# NES_IO_EU.net
KiCad netlist of a schematic drawn in EAGLE
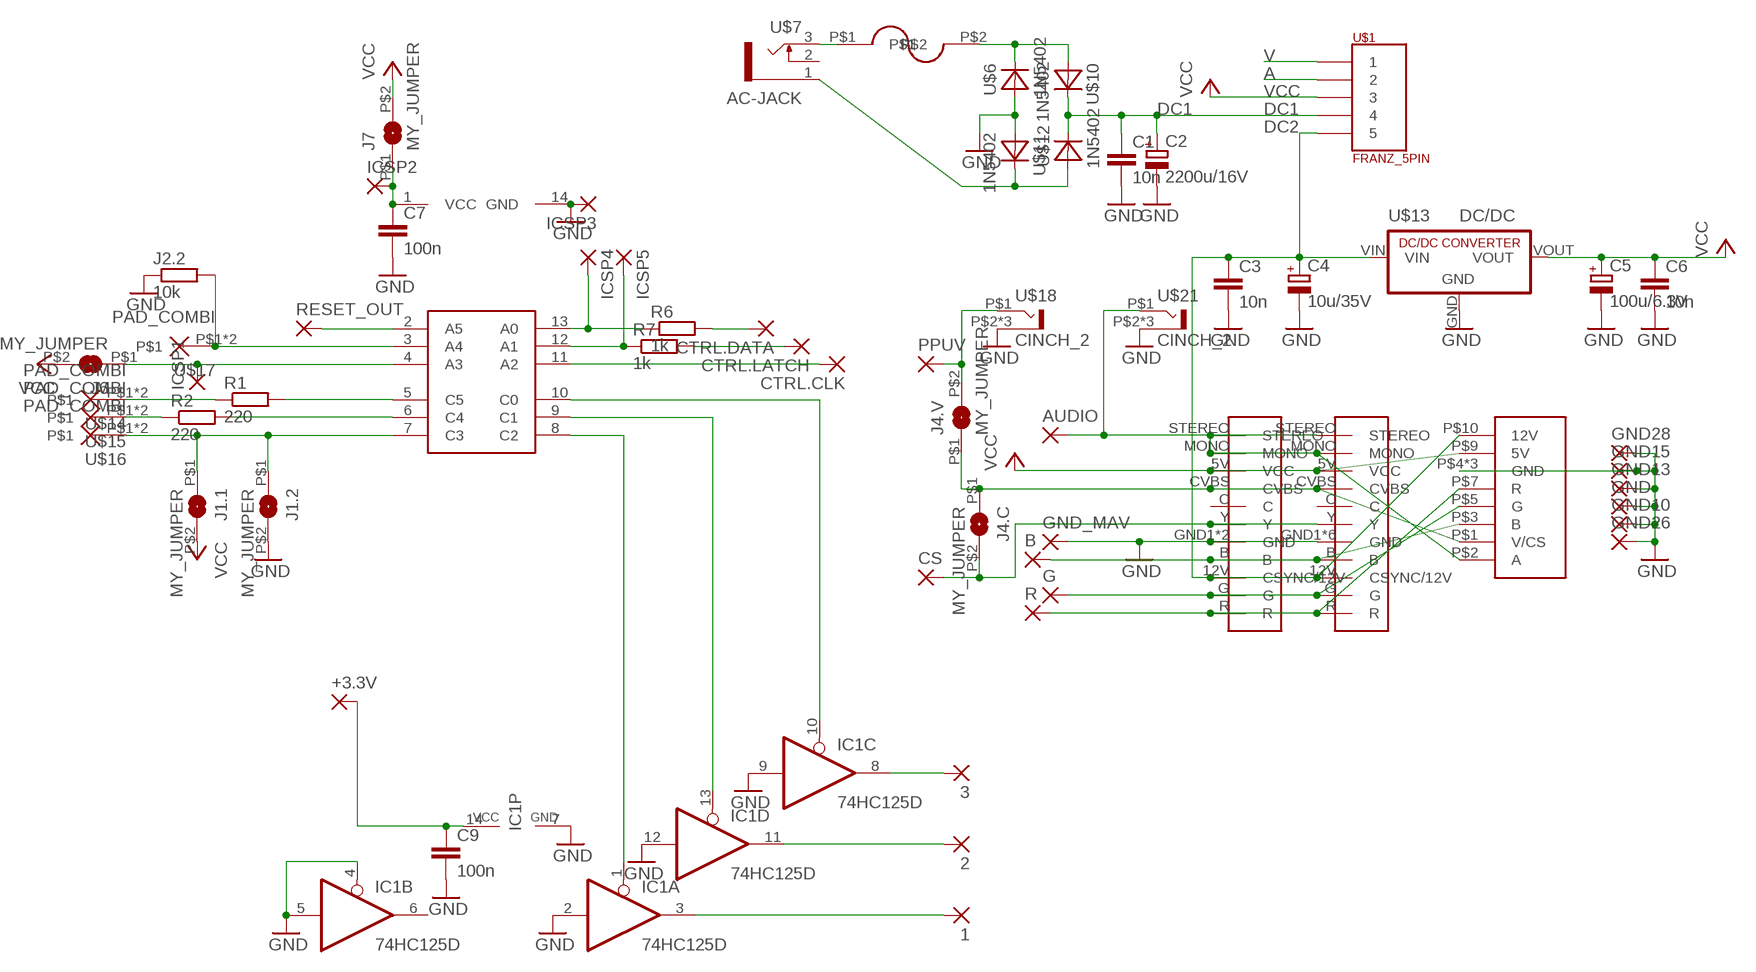
[diagram p0: schematic, sheet 1]

(export (version "E")
  (design (tool "Eeschema 10.0.6"))
  (components
    (comp (ref "+3.3V")
      (value "SMD2")
      (footprint "eagle-import:SMD1,27-2,54")
      (libsource (lib "eagle-import") (part "SMD2"))
    )
    (comp (ref "1")
      (value "SMD2")
      (footprint "eagle-import:SMD1,27-2,54")
      (libsource (lib "eagle-import") (part "SMD2"))
    )
    (comp (ref "2")
      (value "SMD2")
      (footprint "eagle-import:SMD1,27-2,54")
      (libsource (lib "eagle-import") (part "SMD2"))
    )
    (comp (ref "3")
      (value "SMD2")
      (footprint "eagle-import:SMD1,27-2,54")
      (libsource (lib "eagle-import") (part "SMD2"))
    )
    (comp (ref "AUDIO")
      (value "SMD2")
      (footprint "eagle-import:SMD1,27-2,54")
      (libsource (lib "eagle-import") (part "SMD2"))
    )
    (comp (ref "B")
      (value "SMD2")
      (footprint "eagle-import:SMD1,27-2,54")
      (libsource (lib "eagle-import") (part "SMD2"))
    )
    (comp (ref "C1")
      (value "10n")
      (footprint "eagle-import:Z0805")
      (libsource (lib "eagle-import") (part "C0805"))
    )
    (comp (ref "C2")
      (value "2200u/16V")
      (footprint "eagle-import:E5-13")
      (libsource (lib "eagle-import") (part "resistor_CPOL-EUE5-13"))
    )
    (comp (ref "C3")
      (value "10n")
      (footprint "eagle-import:Z0805")
      (libsource (lib "eagle-import") (part "C0805"))
    )
    (comp (ref "C4")
      (value "10u/35V")
      (footprint "eagle-import:PANASONIC_B")
      (libsource (lib "eagle-import") (part "CPOL-EUB"))
    )
    (comp (ref "C5")
      (value "100u/6.3V")
      (footprint "eagle-import:PANASONIC_D")
      (libsource (lib "eagle-import") (part "CPOL-EUD"))
    )
    (comp (ref "C6")
      (value "10n")
      (footprint "eagle-import:Z0805")
      (libsource (lib "eagle-import") (part "C0805"))
    )
    (comp (ref "C7")
      (value "100n")
      (footprint "eagle-import:Z0805")
      (libsource (lib "eagle-import") (part "C0805"))
    )
    (comp (ref "C9")
      (value "100n")
      (footprint "eagle-import:Z0805")
      (libsource (lib "eagle-import") (part "C0805"))
    )
    (comp (ref "CS")
      (value "SMD2")
      (footprint "eagle-import:SMD1,27-2,54")
      (libsource (lib "eagle-import") (part "SMD2"))
    )
    (comp (ref "CTRL.CLK")
      (value "SMD2")
      (footprint "eagle-import:SMD1,27-2,54")
      (libsource (lib "eagle-import") (part "SMD2"))
    )
    (comp (ref "CTRL.DATA")
      (value "SMD2")
      (footprint "eagle-import:SMD1,27-2,54")
      (libsource (lib "eagle-import") (part "SMD2"))
    )
    (comp (ref "CTRL.LATCH")
      (value "SMD2")
      (footprint "eagle-import:SMD1,27-2,54")
      (libsource (lib "eagle-import") (part "SMD2"))
    )
    (comp (ref "G")
      (value "SMD2")
      (footprint "eagle-import:SMD1,27-2,54")
      (libsource (lib "eagle-import") (part "SMD2"))
    )
    (comp (ref "GND")
      (value "SMD5")
      (footprint "eagle-import:SMD2,54-5,08")
      (libsource (lib "eagle-import") (part "SMD5"))
    )
    (comp (ref "GND10")
      (value "SMD5")
      (footprint "eagle-import:SMD2,54-5,08")
      (libsource (lib "eagle-import") (part "SMD5"))
    )
    (comp (ref "GND13")
      (value "SMD5")
      (footprint "eagle-import:SMD2,54-5,08")
      (libsource (lib "eagle-import") (part "SMD5"))
    )
    (comp (ref "GND15")
      (value "SMD5")
      (footprint "eagle-import:SMD2,54-5,08")
      (libsource (lib "eagle-import") (part "SMD5"))
    )
    (comp (ref "GND26")
      (value "SMD5")
      (footprint "eagle-import:SMD2,54-5,08")
      (libsource (lib "eagle-import") (part "SMD5"))
    )
    (comp (ref "GND28")
      (value "SMD5")
      (footprint "eagle-import:SMD2,54-5,08")
      (libsource (lib "eagle-import") (part "SMD5"))
    )
    (comp (ref "GND_MAV")
      (value "SMD2")
      (footprint "eagle-import:SMD1,27-2,54")
      (libsource (lib "eagle-import") (part "SMD2"))
    )
    (comp (ref "IC1")
      (value "74HC125D")
      (footprint "eagle-import:SO14")
      (libsource (lib "eagle-import") (part "74125DHC"))
    )
    (comp (ref "ICSP1")
      (value "1,6/0,8")
      (footprint "eagle-import:1,6_0,8")
      (libsource (lib "eagle-import") (part "1,6/0,8"))
    )
    (comp (ref "ICSP2")
      (value "1,6/0,8")
      (footprint "eagle-import:1,6_0,8")
      (libsource (lib "eagle-import") (part "1,6/0,8"))
    )
    (comp (ref "ICSP3")
      (value "1,6/0,8")
      (footprint "eagle-import:1,6_0,8")
      (libsource (lib "eagle-import") (part "1,6/0,8"))
    )
    (comp (ref "ICSP4")
      (value "1,6/0,8")
      (footprint "eagle-import:1,6_0,8")
      (libsource (lib "eagle-import") (part "1,6/0,8"))
    )
    (comp (ref "ICSP5")
      (value "1,6/0,8")
      (footprint "eagle-import:1,6_0,8")
      (libsource (lib "eagle-import") (part "1,6/0,8"))
    )
    (comp (ref "J1.1")
      (value "MY_JUMPER")
      (footprint "eagle-import:MYJUMP")
      (libsource (lib "eagle-import") (part "MY_JUMPER"))
    )
    (comp (ref "J1.2")
      (value "MY_JUMPER")
      (footprint "eagle-import:MYJUMP")
      (libsource (lib "eagle-import") (part "MY_JUMPER"))
    )
    (comp (ref "J2.2")
      (value "10k")
      (footprint "eagle-import:Z0805")
      (libsource (lib "eagle-import") (part "R0805"))
    )
    (comp (ref "J4.C")
      (value "MY_JUMPER")
      (footprint "eagle-import:MYJUMP")
      (libsource (lib "eagle-import") (part "MY_JUMPER"))
    )
    (comp (ref "J4.V")
      (value "MY_JUMPER")
      (footprint "eagle-import:MYJUMP")
      (libsource (lib "eagle-import") (part "MY_JUMPER"))
    )
    (comp (ref "J6")
      (value "MY_JUMPER")
      (footprint "eagle-import:MYJUMP")
      (libsource (lib "eagle-import") (part "MY_JUMPER"))
    )
    (comp (ref "J7")
      (value "MY_JUMPER")
      (footprint "eagle-import:MYJUMP")
      (libsource (lib "eagle-import") (part "MY_JUMPER"))
    )
    (comp (ref "PPUV")
      (value "SMD2")
      (footprint "eagle-import:SMD1,27-2,54")
      (libsource (lib "eagle-import") (part "SMD2"))
    )
    (comp (ref "R")
      (value "SMD2")
      (footprint "eagle-import:SMD1,27-2,54")
      (libsource (lib "eagle-import") (part "SMD2"))
    )
    (comp (ref "R1")
      (value "220")
      (footprint "eagle-import:Z0805")
      (libsource (lib "eagle-import") (part "R0805"))
    )
    (comp (ref "R2")
      (value "220")
      (footprint "eagle-import:Z0805")
      (libsource (lib "eagle-import") (part "R0805"))
    )
    (comp (ref "R6")
      (value "1k")
      (footprint "eagle-import:Z0805")
      (libsource (lib "eagle-import") (part "R0805"))
    )
    (comp (ref "R7")
      (value "1k")
      (footprint "eagle-import:Z0805")
      (libsource (lib "eagle-import") (part "R0805"))
    )
    (comp (ref "RESET_OUT")
      (value "SMD2")
      (footprint "eagle-import:SMD1,27-2,54")
      (libsource (lib "eagle-import") (part "SMD2"))
    )
    (comp (ref "U$1")
      (value "FRANZ_5PIN")
      (footprint "eagle-import:5X2.22RM4")
      (libsource (lib "eagle-import") (part "FRANZ_5PIN"))
    )
    (comp (ref "U$2")
      (value "FUSEHOLDER")
      (footprint "eagle-import:FUSEHOLDER")
      (libsource (lib "eagle-import") (part "FUSEHOLDER"))
    )
    (comp (ref "U$5")
      (value "PIC16F630_SIMPLE")
      (footprint "eagle-import:PIC16F630")
      (libsource (lib "eagle-import") (part "PIC16F630_SIMPLE"))
    )
    (comp (ref "U$6")
      (value "1N5402")
      (footprint "eagle-import:DO201")
      (libsource (lib "eagle-import") (part "1N5402"))
    )
    (comp (ref "U$7")
      (value "AC-JACK")
      (footprint "eagle-import:AC-JACK")
      (libsource (lib "eagle-import") (part "AC-JACK"))
    )
    (comp (ref "U$8")
      (value "NESFR_JACK2")
      (footprint "eagle-import:NESFR_JACK2")
      (libsource (lib "eagle-import") (part "NESFR_JACK2"))
    )
    (comp (ref "U$10")
      (value "1N5402")
      (footprint "eagle-import:DO201")
      (libsource (lib "eagle-import") (part "1N5402"))
    )
    (comp (ref "U$11")
      (value "1N5402")
      (footprint "eagle-import:DO201")
      (libsource (lib "eagle-import") (part "1N5402"))
    )
    (comp (ref "U$12")
      (value "1N5402")
      (footprint "eagle-import:DO201")
      (libsource (lib "eagle-import") (part "1N5402"))
    )
    (comp (ref "U$13")
      (value "DC/DC")
      (footprint "eagle-import:RECOM")
      (libsource (lib "eagle-import") (part "DC/DC"))
    )
    (comp (ref "U$14")
      (value "PAD_COMBI")
      (footprint "eagle-import:PAD_COMBI")
      (libsource (lib "eagle-import") (part "PAD_COMBI"))
    )
    (comp (ref "U$15")
      (value "PAD_COMBI")
      (footprint "eagle-import:PAD_COMBI")
      (libsource (lib "eagle-import") (part "PAD_COMBI"))
    )
    (comp (ref "U$16")
      (value "PAD_COMBI")
      (footprint "eagle-import:PAD_COMBI")
      (libsource (lib "eagle-import") (part "PAD_COMBI"))
    )
    (comp (ref "U$17")
      (value "PAD_COMBI")
      (footprint "eagle-import:PAD_COMBI")
      (libsource (lib "eagle-import") (part "PAD_COMBI"))
    )
    (comp (ref "U$18")
      (value "CINCH_2")
      (footprint "eagle-import:CINCH_2")
      (libsource (lib "eagle-import") (part "CINCH_2"))
    )
    (comp (ref "U$19")
      (value "GC-MULTIAV")
      (footprint "eagle-import:GC-MULTIAV")
      (libsource (lib "eagle-import") (part "GC-MULTIAV"))
    )
    (comp (ref "U$20")
      (value "SNES-MULTIAV2")
      (footprint "eagle-import:SNES-MULTIAV2")
      (libsource (lib "eagle-import") (part "SNES-MULTIAV2"))
    )
    (comp (ref "U$21")
      (value "CINCH_2")
      (footprint "eagle-import:CINCH_2")
      (libsource (lib "eagle-import") (part "CINCH_2"))
    )
  )
  (nets
    (net (code "1") (name "/A") (class "Default")
      (node (ref "U$1") (pin "P$2") (pinfunction "2_P$2") (pintype "bidirectional"))
    )
    (net (code "2") (name "/DC1") (class "Default")
      (node (ref "C1") (pin "1") (pinfunction "1_1") (pintype "passive"))
      (node (ref "C2") (pin "+") (pinfunction "+_+") (pintype "passive"))
      (node (ref "U$1") (pin "P$4") (pinfunction "4_P$4") (pintype "bidirectional"))
      (node (ref "U$10") (pin "C") (pinfunction "C_C") (pintype "passive"))
      (node (ref "U$12") (pin "C") (pinfunction "C_C") (pintype "passive"))
    )
    (net (code "3") (name "/DC2") (class "Default")
      (node (ref "C3") (pin "1") (pinfunction "1_1") (pintype "passive"))
      (node (ref "C4") (pin "+") (pinfunction "+_+") (pintype "passive"))
      (node (ref "U$1") (pin "P$5") (pinfunction "5_P$5") (pintype "bidirectional"))
      (node (ref "U$13") (pin "VIN") (pinfunction "VIN_VIN") (pintype "passive"))
      (node (ref "U$19") (pin "12V") (pinfunction "CSYNC/12V_12V") (pintype "output"))
      (node (ref "U$20") (pin "12V") (pinfunction "CSYNC/12V_12V") (pintype "output"))
      (node (ref "U$8") (pin "P$10") (pinfunction "12V_P$10") (pintype "bidirectional"))
    )
    (net (code "4") (name "/V") (class "Default")
      (node (ref "U$1") (pin "P$1") (pinfunction "1_P$1") (pintype "bidirectional"))
    )
    (net (code "5") (name "GND") (class "Default")
      (node (ref "C1") (pin "2") (pinfunction "2_2") (pintype "passive"))
      (node (ref "C2") (pin "-") (pinfunction "-_-") (pintype "passive"))
      (node (ref "C3") (pin "2") (pinfunction "2_2") (pintype "passive"))
      (node (ref "C4") (pin "-") (pinfunction "-_-") (pintype "passive"))
      (node (ref "C5") (pin "-") (pinfunction "-_-") (pintype "passive"))
      (node (ref "C6") (pin "2") (pinfunction "2_2") (pintype "passive"))
      (node (ref "C7") (pin "2") (pinfunction "2_2") (pintype "passive"))
      (node (ref "C9") (pin "2") (pinfunction "2_2") (pintype "passive"))
      (node (ref "GND") (pin "1") (pinfunction "P_1") (pintype "passive"))
      (node (ref "GND10") (pin "1") (pinfunction "P_1") (pintype "passive"))
      (node (ref "GND13") (pin "1") (pinfunction "P_1") (pintype "passive"))
      (node (ref "GND15") (pin "1") (pinfunction "P_1") (pintype "passive"))
      (node (ref "GND26") (pin "1") (pinfunction "P_1") (pintype "passive"))
      (node (ref "GND28") (pin "1") (pinfunction "P_1") (pintype "passive"))
      (node (ref "GND_MAV") (pin "1") (pinfunction "P_1") (pintype "passive"))
      (node (ref "IC1") (pin "12") (pinfunction "I_12") (pintype "input"))
      (node (ref "IC1") (pin "2") (pinfunction "I_2") (pintype "input"))
      (node (ref "IC1") (pin "4") (pinfunction "OE_4") (pintype "input"))
      (node (ref "IC1") (pin "5") (pinfunction "I_5") (pintype "input"))
      (node (ref "IC1") (pin "7") (pinfunction "GND_7") (pintype "power_in"))
      (node (ref "IC1") (pin "9") (pinfunction "I_9") (pintype "input"))
      (node (ref "ICSP3") (pin "1") (pinfunction "P_1") (pintype "passive"))
      (node (ref "J1.2") (pin "P$2") (pinfunction "2_P$2") (pintype "passive"))
      (node (ref "J2.2") (pin "1") (pinfunction "1_1") (pintype "passive"))
      (node (ref "U$11") (pin "A") (pinfunction "A_A") (pintype "passive"))
      (node (ref "U$13") (pin "GND") (pinfunction "GND_GND") (pintype "passive"))
      (node (ref "U$18") (pin "P$2") (pinfunction "S_P$2") (pintype "passive"))
      (node (ref "U$18") (pin "P$3") (pinfunction "S_P$3") (pintype "passive"))
      (node (ref "U$18") (pin "P$4") (pinfunction "S_P$4") (pintype "passive"))
      (node (ref "U$19") (pin "GND1") (pinfunction "GND_GND1") (pintype "output"))
      (node (ref "U$19") (pin "GND2") (pinfunction "GND_GND2") (pintype "output"))
      (node (ref "U$19") (pin "GND3") (pinfunction "GND_GND3") (pintype "output"))
      (node (ref "U$19") (pin "GND4") (pinfunction "GND_GND4") (pintype "output"))
      (node (ref "U$19") (pin "GND5") (pinfunction "GND_GND5") (pintype "output"))
      (node (ref "U$19") (pin "GND6") (pinfunction "GND_GND6") (pintype "output"))
      (node (ref "U$20") (pin "GND1") (pinfunction "GND_GND1") (pintype "output"))
      (node (ref "U$20") (pin "GND2") (pinfunction "GND_GND2") (pintype "output"))
      (node (ref "U$21") (pin "P$2") (pinfunction "S_P$2") (pintype "passive"))
      (node (ref "U$21") (pin "P$3") (pinfunction "S_P$3") (pintype "passive"))
      (node (ref "U$21") (pin "P$4") (pinfunction "S_P$4") (pintype "passive"))
      (node (ref "U$5") (pin "14") (pinfunction "GND_14") (pintype "bidirectional"))
      (node (ref "U$6") (pin "A") (pinfunction "A_A") (pintype "passive"))
      (node (ref "U$8") (pin "P$4") (pinfunction "GND_P$4") (pintype "bidirectional"))
      (node (ref "U$8") (pin "P$6") (pinfunction "GND_P$6") (pintype "bidirectional"))
      (node (ref "U$8") (pin "P$8") (pinfunction "GND_P$8") (pintype "bidirectional"))
    )
    (net (code "6") (name "Net-(+3.3V-P)") (class "Default")
      (node (ref "+3.3V") (pin "1") (pinfunction "P_1") (pintype "passive"))
      (node (ref "C9") (pin "1") (pinfunction "1_1") (pintype "passive"))
      (node (ref "IC1") (pin "14") (pinfunction "VCC_14") (pintype "power_in"))
    )
    (net (code "7") (name "Net-(1-P)") (class "Default")
      (node (ref "1") (pin "1") (pinfunction "P_1") (pintype "passive"))
      (node (ref "IC1") (pin "3") (pinfunction "O_3") (pintype "tri_state"))
    )
    (net (code "8") (name "Net-(2-P)") (class "Default")
      (node (ref "2") (pin "1") (pinfunction "P_1") (pintype "passive"))
      (node (ref "IC1") (pin "11") (pinfunction "O_11") (pintype "tri_state"))
    )
    (net (code "9") (name "Net-(3-P)") (class "Default")
      (node (ref "3") (pin "1") (pinfunction "P_1") (pintype "passive"))
      (node (ref "IC1") (pin "8") (pinfunction "O_8") (pintype "tri_state"))
    )
    (net (code "10") (name "Net-(AUDIO-P)") (class "Default")
      (node (ref "AUDIO") (pin "1") (pinfunction "P_1") (pintype "passive"))
      (node (ref "U$19") (pin "MONO") (pinfunction "MONO_MONO") (pintype "output"))
      (node (ref "U$19") (pin "STEREO") (pinfunction "STEREO_STEREO") (pintype "output"))
      (node (ref "U$20") (pin "MONO") (pinfunction "MONO_MONO") (pintype "output"))
      (node (ref "U$20") (pin "STEREO") (pinfunction "STEREO_STEREO") (pintype "output"))
      (node (ref "U$21") (pin "P$1") (pinfunction "T_P$1") (pintype "passive"))
      (node (ref "U$8") (pin "P$2") (pinfunction "A_P$2") (pintype "bidirectional"))
    )
    (net (code "11") (name "Net-(B-P)") (class "Default")
      (node (ref "B") (pin "1") (pinfunction "P_1") (pintype "passive"))
      (node (ref "U$19") (pin "B") (pinfunction "B_B") (pintype "output"))
      (node (ref "U$20") (pin "B") (pinfunction "B_B") (pintype "output"))
      (node (ref "U$8") (pin "P$3") (pinfunction "B_P$3") (pintype "bidirectional"))
    )
    (net (code "12") (name "Net-(CS-P)") (class "Default")
      (node (ref "CS") (pin "1") (pinfunction "P_1") (pintype "passive"))
      (node (ref "J4.C") (pin "P$2") (pinfunction "2_P$2") (pintype "passive"))
      (node (ref "U$19") (pin "Y") (pinfunction "Y_Y") (pintype "output"))
      (node (ref "U$20") (pin "Y") (pinfunction "Y_Y") (pintype "output"))
    )
    (net (code "13") (name "Net-(CTRL.CLK-P)") (class "Default")
      (node (ref "CTRL.CLK") (pin "1") (pinfunction "P_1") (pintype "passive"))
      (node (ref "U$5") (pin "11") (pinfunction "A2_11") (pintype "bidirectional"))
    )
    (net (code "14") (name "Net-(CTRL.DATA-P)") (class "Default")
      (node (ref "CTRL.DATA") (pin "1") (pinfunction "P_1") (pintype "passive"))
      (node (ref "R6") (pin "2") (pinfunction "2_2") (pintype "passive"))
    )
    (net (code "15") (name "Net-(CTRL.LATCH-P)") (class "Default")
      (node (ref "CTRL.LATCH") (pin "1") (pinfunction "P_1") (pintype "passive"))
      (node (ref "R7") (pin "2") (pinfunction "2_2") (pintype "passive"))
    )
    (net (code "16") (name "Net-(G-P)") (class "Default")
      (node (ref "G") (pin "1") (pinfunction "P_1") (pintype "passive"))
      (node (ref "U$19") (pin "G") (pinfunction "G_G") (pintype "output"))
      (node (ref "U$20") (pin "G") (pinfunction "G_G") (pintype "output"))
      (node (ref "U$8") (pin "P$5") (pinfunction "G_P$5") (pintype "bidirectional"))
    )
    (net (code "17") (name "Net-(IC1A-OE)") (class "Default")
      (node (ref "IC1") (pin "1") (pinfunction "OE_1") (pintype "input"))
      (node (ref "U$5") (pin "8") (pinfunction "C2_8") (pintype "bidirectional"))
    )
    (net (code "18") (name "Net-(IC1C-OE)") (class "Default")
      (node (ref "IC1") (pin "10") (pinfunction "OE_10") (pintype "input"))
      (node (ref "U$5") (pin "10") (pinfunction "C0_10") (pintype "bidirectional"))
    )
    (net (code "19") (name "Net-(IC1D-OE)") (class "Default")
      (node (ref "IC1") (pin "13") (pinfunction "OE_13") (pintype "input"))
      (node (ref "U$5") (pin "9") (pinfunction "C1_9") (pintype "bidirectional"))
    )
    (net (code "20") (name "Net-(ICSP1-P)") (class "Default")
      (node (ref "ICSP1") (pin "1") (pinfunction "P_1") (pintype "passive"))
      (node (ref "J6") (pin "P$1") (pinfunction "1_P$1") (pintype "passive"))
      (node (ref "U$5") (pin "4") (pinfunction "A3_4") (pintype "bidirectional"))
    )
    (net (code "21") (name "Net-(ICSP2-P)") (class "Default")
      (node (ref "C7") (pin "1") (pinfunction "1_1") (pintype "passive"))
      (node (ref "ICSP2") (pin "1") (pinfunction "P_1") (pintype "passive"))
      (node (ref "J7") (pin "P$1") (pinfunction "1_P$1") (pintype "passive"))
      (node (ref "U$5") (pin "1") (pinfunction "VCC_1") (pintype "bidirectional"))
    )
    (net (code "22") (name "Net-(ICSP4-P)") (class "Default")
      (node (ref "ICSP4") (pin "1") (pinfunction "P_1") (pintype "passive"))
      (node (ref "R6") (pin "1") (pinfunction "1_1") (pintype "passive"))
      (node (ref "U$5") (pin "13") (pinfunction "A0_13") (pintype "bidirectional"))
    )
    (net (code "23") (name "Net-(ICSP5-P)") (class "Default")
      (node (ref "ICSP5") (pin "1") (pinfunction "P_1") (pintype "passive"))
      (node (ref "R7") (pin "1") (pinfunction "1_1") (pintype "passive"))
      (node (ref "U$5") (pin "12") (pinfunction "A1_12") (pintype "bidirectional"))
    )
    (net (code "24") (name "Net-(J1.1-1)") (class "Default")
      (node (ref "J1.1") (pin "P$1") (pinfunction "1_P$1") (pintype "passive"))
      (node (ref "J1.2") (pin "P$1") (pinfunction "1_P$1") (pintype "passive"))
      (node (ref "U$16") (pin "P$1") (pinfunction "P$1_P$1") (pintype "bidirectional"))
      (node (ref "U$16") (pin "P$2") (pinfunction "P$1_P$2") (pintype "bidirectional"))
      (node (ref "U$5") (pin "7") (pinfunction "C3_7") (pintype "bidirectional"))
    )
    (net (code "25") (name "Net-(J4.C-1)") (class "Default")
      (node (ref "J4.C") (pin "P$1") (pinfunction "1_P$1") (pintype "passive"))
      (node (ref "J4.V") (pin "P$1") (pinfunction "1_P$1") (pintype "passive"))
      (node (ref "U$19") (pin "CVBS") (pinfunction "CVBS_CVBS") (pintype "output"))
      (node (ref "U$20") (pin "CVBS") (pinfunction "CVBS_CVBS") (pintype "output"))
      (node (ref "U$8") (pin "P$1") (pinfunction "V/CS_P$1") (pintype "bidirectional"))
    )
    (net (code "26") (name "Net-(J4.V-2)") (class "Default")
      (node (ref "J4.V") (pin "P$2") (pinfunction "2_P$2") (pintype "passive"))
      (node (ref "PPUV") (pin "1") (pinfunction "P_1") (pintype "passive"))
      (node (ref "U$18") (pin "P$1") (pinfunction "T_P$1") (pintype "passive"))
    )
    (net (code "27") (name "Net-(R-P)") (class "Default")
      (node (ref "R") (pin "1") (pinfunction "P_1") (pintype "passive"))
      (node (ref "U$19") (pin "R") (pinfunction "R_R") (pintype "output"))
      (node (ref "U$20") (pin "R") (pinfunction "R_R") (pintype "output"))
      (node (ref "U$8") (pin "P$7") (pinfunction "R_P$7") (pintype "bidirectional"))
    )
    (net (code "28") (name "Net-(R1-Pad1)") (class "Default")
      (node (ref "R1") (pin "1") (pinfunction "1_1") (pintype "passive"))
      (node (ref "U$14") (pin "P$1") (pinfunction "P$1_P$1") (pintype "bidirectional"))
      (node (ref "U$14") (pin "P$2") (pinfunction "P$1_P$2") (pintype "bidirectional"))
    )
    (net (code "29") (name "Net-(R2-Pad1)") (class "Default")
      (node (ref "R2") (pin "1") (pinfunction "1_1") (pintype "passive"))
      (node (ref "U$15") (pin "P$1") (pinfunction "P$1_P$1") (pintype "bidirectional"))
      (node (ref "U$15") (pin "P$2") (pinfunction "P$1_P$2") (pintype "bidirectional"))
    )
    (net (code "30") (name "Net-(RESET_OUT-P)") (class "Default")
      (node (ref "RESET_OUT") (pin "1") (pinfunction "P_1") (pintype "passive"))
      (node (ref "U$5") (pin "2") (pinfunction "A5_2") (pintype "bidirectional"))
    )
    (net (code "31") (name "Net-(U$2-PadP$1)") (class "Default")
      (node (ref "U$2") (pin "P$1") (pinfunction "P$1_P$1") (pintype "bidirectional"))
      (node (ref "U$7") (pin "3") (pinfunction "3_3") (pintype "passive"))
    )
    (net (code "32") (name "Net-(U$5A-A4)") (class "Default")
      (node (ref "J2.2") (pin "2") (pinfunction "2_2") (pintype "passive"))
      (node (ref "U$17") (pin "P$1") (pinfunction "P$1_P$1") (pintype "bidirectional"))
      (node (ref "U$17") (pin "P$2") (pinfunction "P$1_P$2") (pintype "bidirectional"))
      (node (ref "U$5") (pin "3") (pinfunction "A4_3") (pintype "bidirectional"))
    )
    (net (code "33") (name "Net-(U$5A-C4)") (class "Default")
      (node (ref "R2") (pin "2") (pinfunction "2_2") (pintype "passive"))
      (node (ref "U$5") (pin "6") (pinfunction "C4_6") (pintype "bidirectional"))
    )
    (net (code "34") (name "Net-(U$5A-C5)") (class "Default")
      (node (ref "R1") (pin "2") (pinfunction "2_2") (pintype "passive"))
      (node (ref "U$5") (pin "5") (pinfunction "C5_5") (pintype "bidirectional"))
    )
    (net (code "35") (name "Net-(U$7-5)") (class "Default")
      (node (ref "U$11") (pin "C") (pinfunction "C_C") (pintype "passive"))
      (node (ref "U$12") (pin "A") (pinfunction "A_A") (pintype "passive"))
      (node (ref "U$7") (pin "1") (pinfunction "5_1") (pintype "passive"))
    )
    (net (code "36") (name "Net-(U$10-PadA)") (class "Default")
      (node (ref "U$10") (pin "A") (pinfunction "A_A") (pintype "passive"))
      (node (ref "U$2") (pin "P$2") (pinfunction "P$2_P$2") (pintype "bidirectional"))
      (node (ref "U$6") (pin "C") (pinfunction "C_C") (pintype "passive"))
    )
    (net (code "37") (name "VCC") (class "Default")
      (node (ref "C5") (pin "+") (pinfunction "+_+") (pintype "passive"))
      (node (ref "C6") (pin "1") (pinfunction "1_1") (pintype "passive"))
      (node (ref "J1.1") (pin "P$2") (pinfunction "2_P$2") (pintype "passive"))
      (node (ref "J6") (pin "P$2") (pinfunction "2_P$2") (pintype "passive"))
      (node (ref "J7") (pin "P$2") (pinfunction "2_P$2") (pintype "passive"))
      (node (ref "U$1") (pin "P$3") (pinfunction "3_P$3") (pintype "bidirectional"))
      (node (ref "U$13") (pin "VOUT") (pinfunction "VOUT_VOUT") (pintype "passive"))
      (node (ref "U$19") (pin "5V") (pinfunction "VCC_5V") (pintype "output"))
      (node (ref "U$20") (pin "5V") (pinfunction "VCC_5V") (pintype "output"))
      (node (ref "U$8") (pin "P$9") (pinfunction "5V_P$9") (pintype "bidirectional"))
    )
    (net (code "38") (name "unconnected-(IC1B-O-Pad6)") (class "Default")
      (node (ref "IC1") (pin "6") (pinfunction "O_6") (pintype "tri_state"))
    )
    (net (code "39") (name "unconnected-(U$7-4-Pad2)") (class "Default")
      (node (ref "U$7") (pin "2") (pinfunction "4_2") (pintype "passive"))
    )
    (net (code "40") (name "unconnected-(U$19-PadC)") (class "Default")
      (node (ref "U$19") (pin "C") (pinfunction "C_C") (pintype "output"))
    )
    (net (code "41") (name "unconnected-(U$20-PadC)") (class "Default")
      (node (ref "U$20") (pin "C") (pinfunction "C_C") (pintype "output"))
    )
  )
)
